# I2C_Keypad.net
KiCad netlist of a schematic drawn in Altium Designer
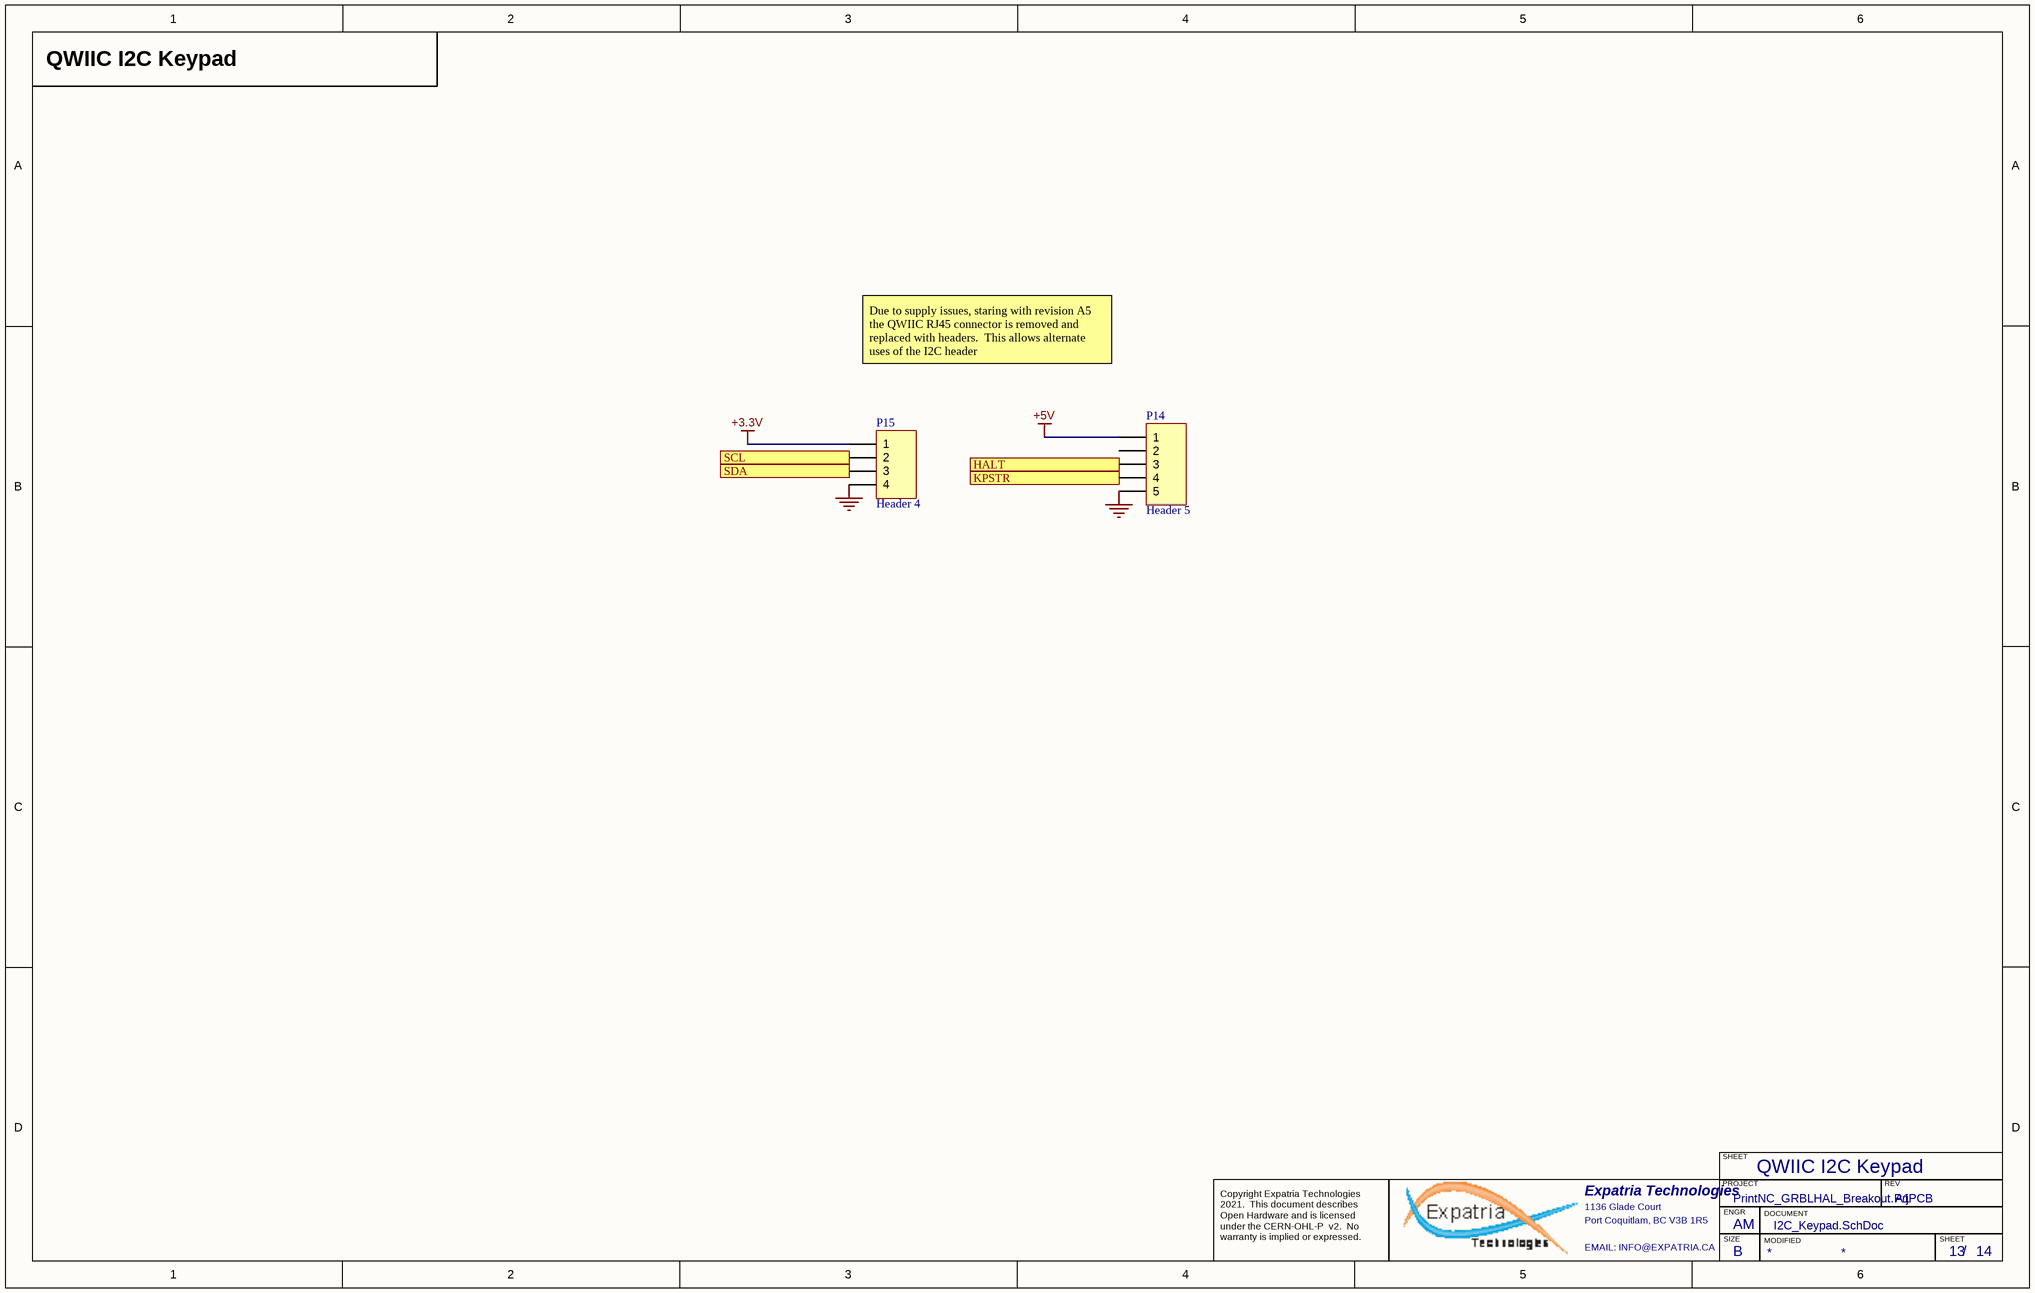
[diagram p0: I2C_Keypad.SchDoc]

(export (version "E")
  (design (tool "Eeschema 10.0.6"))
  (components
    (comp (ref "P14")
      (value "Header 5")
      (footprint "HDR1X5")
      (description "Header, 5-Pin")
      (fields (field (name "PUBLISHER") "Altium Limited"))
      (libsource (lib "PrintNC_GRBLHAL_Breakout") (part "Header 5"))
    )
    (comp (ref "P15")
      (value "Header 4")
      (footprint "HDR1X4")
      (description "Header, 4-Pin")
      (fields (field (name "PUBLISHER") "Altium Limited"))
      (libsource (lib "PrintNC_GRBLHAL_Breakout") (part "Header 4"))
    )
  )
  (nets
    (net (code "1") (name "+3.3V") (class "Default")
      (node (ref "P15") (pin "1") (pinfunction "1_1") (pintype "passive"))
    )
    (net (code "2") (name "+5V") (class "Default")
      (node (ref "P14") (pin "1") (pinfunction "1_1") (pintype "passive"))
    )
    (net (code "3") (name "/HALT") (class "Default")
      (node (ref "P14") (pin "3") (pinfunction "3_3") (pintype "passive"))
    )
    (net (code "4") (name "/KPSTR") (class "Default")
      (node (ref "P14") (pin "4") (pinfunction "4_4") (pintype "passive"))
    )
    (net (code "5") (name "/SCL") (class "Default")
      (node (ref "P15") (pin "2") (pinfunction "2_2") (pintype "passive"))
    )
    (net (code "6") (name "/SDA") (class "Default")
      (node (ref "P15") (pin "3") (pinfunction "3_3") (pintype "passive"))
    )
    (net (code "7") (name "GND") (class "Default")
      (node (ref "P14") (pin "5") (pinfunction "5_5") (pintype "passive"))
      (node (ref "P15") (pin "4") (pinfunction "4_4") (pintype "passive"))
    )
    (net (code "8") (name "unconnected-(P14-Pad2)") (class "Default")
      (node (ref "P14") (pin "2") (pinfunction "2_2") (pintype "passive"))
    )
  )
)
